# powerpartial_proto2.net
KiCad netlist of a schematic drawn in EAGLE
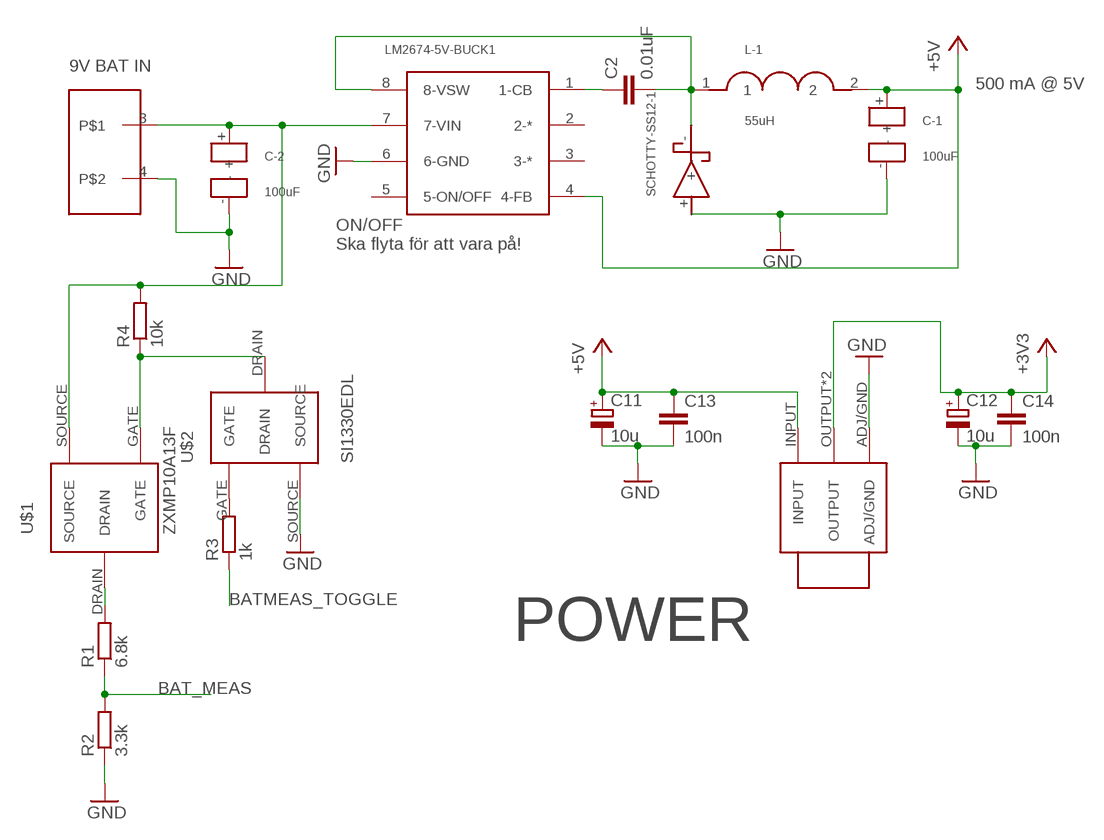
[diagram p0: schematic, sheet 1]

(export (version "E")
  (design (tool "Eeschema 10.0.6"))
  (components
    (comp (ref "C-1")
      (value "100uF")
      (footprint "eagle-import:CAP-6.3MM-DIA")
      (libsource (lib "eagle-import") (part "PANASONIC-CAP"))
    )
    (comp (ref "C-2")
      (value "100uF")
      (footprint "eagle-import:CAP-6.3MM-DIA")
      (libsource (lib "eagle-import") (part "PANASONIC-CAP"))
    )
    (comp (ref "C2")
      (value "0.01uF")
      (footprint "eagle-import:C0805")
      (libsource (lib "eagle-import") (part "C-EUC0805"))
    )
    (comp (ref "C11")
      (value "10u")
      (footprint "eagle-import:153CLV-0505")
      (libsource (lib "eagle-import") (part "CPOL-EU153CLV-0505"))
    )
    (comp (ref "C12")
      (value "10u")
      (footprint "eagle-import:153CLV-0505")
      (libsource (lib "eagle-import") (part "CPOL-EU153CLV-0505"))
    )
    (comp (ref "C13")
      (value "100n")
      (footprint "eagle-import:C0805")
      (libsource (lib "eagle-import") (part "C-EUC0805"))
    )
    (comp (ref "C14")
      (value "100n")
      (footprint "eagle-import:C0805")
      (libsource (lib "eagle-import") (part "C-EUC0805"))
    )
    (comp (ref "L-1")
      (value "55uH")
      (footprint "eagle-import:INDUCTOR")
      (libsource (lib "eagle-import") (part "55UH-INDUKTOR"))
    )
    (comp (ref "LM1117-1")
      (value "LM1117")
      (footprint "eagle-import:LM1117")
      (libsource (lib "eagle-import") (part "LM1117"))
    )
    (comp (ref "LM2674-5V-BUCK1")
      (value "LM2674-5VBUCK")
      (footprint "eagle-import:LM2674")
      (libsource (lib "eagle-import") (part "LM2674-5VBUCK"))
    )
    (comp (ref "R1")
      (value "6.8k")
      (footprint "eagle-import:R0805")
      (libsource (lib "eagle-import") (part "R-EU_R0805"))
    )
    (comp (ref "R2")
      (value "3.3k")
      (footprint "eagle-import:R0805")
      (libsource (lib "eagle-import") (part "R-EU_R0805"))
    )
    (comp (ref "R3")
      (value "1k")
      (footprint "eagle-import:R0805")
      (libsource (lib "eagle-import") (part "R-EU_R0805"))
    )
    (comp (ref "R4")
      (value "10k")
      (footprint "eagle-import:R0805")
      (libsource (lib "eagle-import") (part "R-EU_R0805"))
    )
    (comp (ref "SCHOTTY-SS12-1")
      (value "SCHOTTY-SS12")
      (footprint "eagle-import:SCHOTTY")
      (libsource (lib "eagle-import") (part "SCHOTTY-SS12"))
    )
    (comp (ref "SKRUVPLINT_2P1")
      (value "SKRUVPLINT_2P")
      (footprint "eagle-import:SKRUVPLINT_2P")
      (libsource (lib "eagle-import") (part "SKRUVPLINT_2P"))
    )
    (comp (ref "U$1")
      (value "ZXMP10A13F")
      (footprint "eagle-import:P-CHANNEL")
      (libsource (lib "eagle-import") (part "ZXMP10A13F"))
    )
    (comp (ref "U$2")
      (value "SI1330EDL")
      (footprint "eagle-import:SOT-323")
      (libsource (lib "eagle-import") (part "SI1330EDL"))
    )
  )
  (nets
    (net (code "1") (name "+3V3") (class "Default")
      (node (ref "C12") (pin "+") (pinfunction "+_+") (pintype "passive"))
      (node (ref "C14") (pin "1") (pinfunction "1_1") (pintype "passive"))
      (node (ref "LM1117-1") (pin "OUTPUT") (pinfunction "OUTPUT_OUTPUT") (pintype "bidirectional"))
      (node (ref "LM1117-1") (pin "OUTPUT2") (pinfunction "OUTPUT_OUTPUT2") (pintype "bidirectional"))
    )
    (net (code "2") (name "+5V") (class "Default")
      (node (ref "C-1") (pin "+") (pinfunction "+_+") (pintype "bidirectional"))
      (node (ref "C11") (pin "+") (pinfunction "+_+") (pintype "passive"))
      (node (ref "C13") (pin "1") (pinfunction "1_1") (pintype "passive"))
      (node (ref "L-1") (pin "2") (pinfunction "2_2") (pintype "bidirectional"))
      (node (ref "LM1117-1") (pin "INPUT") (pinfunction "INPUT_INPUT") (pintype "bidirectional"))
      (node (ref "LM2674-5V-BUCK1") (pin "4") (pinfunction "4-FB_4") (pintype "bidirectional"))
    )
    (net (code "3") (name "/BATMEAS_TOGGLE") (class "Default")
      (node (ref "R3") (pin "1") (pinfunction "1_1") (pintype "passive"))
    )
    (net (code "4") (name "/BAT_MEAS") (class "Default")
      (node (ref "R1") (pin "1") (pinfunction "1_1") (pintype "passive"))
      (node (ref "R2") (pin "2") (pinfunction "2_2") (pintype "passive"))
    )
    (net (code "5") (name "GND") (class "Default")
      (node (ref "C-1") (pin "-") (pinfunction "-_-") (pintype "bidirectional"))
      (node (ref "C-2") (pin "-") (pinfunction "-_-") (pintype "bidirectional"))
      (node (ref "C11") (pin "-") (pinfunction "-_-") (pintype "passive"))
      (node (ref "C12") (pin "-") (pinfunction "-_-") (pintype "passive"))
      (node (ref "C13") (pin "2") (pinfunction "2_2") (pintype "passive"))
      (node (ref "C14") (pin "2") (pinfunction "2_2") (pintype "passive"))
      (node (ref "LM1117-1") (pin "ADJ/GND") (pinfunction "ADJ/GND_ADJ/GND") (pintype "bidirectional"))
      (node (ref "LM2674-5V-BUCK1") (pin "6") (pinfunction "6-GND_6") (pintype "bidirectional"))
      (node (ref "R2") (pin "1") (pinfunction "1_1") (pintype "passive"))
      (node (ref "SCHOTTY-SS12-1") (pin "+") (pinfunction "+_+") (pintype "bidirectional"))
      (node (ref "SKRUVPLINT_2P1") (pin "4") (pinfunction "P$2_4") (pintype "bidirectional"))
      (node (ref "U$2") (pin "SOURCE") (pinfunction "SOURCE_SOURCE") (pintype "bidirectional"))
    )
    (net (code "6") (name "Net-(LM2674-5V-BUCK1-1-CB)") (class "Default")
      (node (ref "C2") (pin "1") (pinfunction "1_1") (pintype "passive"))
      (node (ref "LM2674-5V-BUCK1") (pin "1") (pinfunction "1-CB_1") (pintype "bidirectional"))
    )
    (net (code "7") (name "Net-(LM2674-5V-BUCK1-7-VIN)") (class "Default")
      (node (ref "C-2") (pin "+") (pinfunction "+_+") (pintype "bidirectional"))
      (node (ref "LM2674-5V-BUCK1") (pin "7") (pinfunction "7-VIN_7") (pintype "bidirectional"))
      (node (ref "R4") (pin "2") (pinfunction "2_2") (pintype "passive"))
      (node (ref "SKRUVPLINT_2P1") (pin "3") (pinfunction "P$1_3") (pintype "bidirectional"))
      (node (ref "U$1") (pin "SOURCE") (pinfunction "SOURCE_SOURCE") (pintype "bidirectional"))
    )
    (net (code "8") (name "Net-(LM2674-5V-BUCK1-8-VSW)") (class "Default")
      (node (ref "C2") (pin "2") (pinfunction "2_2") (pintype "passive"))
      (node (ref "L-1") (pin "1") (pinfunction "1_1") (pintype "bidirectional"))
      (node (ref "LM2674-5V-BUCK1") (pin "8") (pinfunction "8-VSW_8") (pintype "bidirectional"))
      (node (ref "SCHOTTY-SS12-1") (pin "-") (pinfunction "-_-") (pintype "bidirectional"))
    )
    (net (code "9") (name "Net-(R1-Pad2)") (class "Default")
      (node (ref "R1") (pin "2") (pinfunction "2_2") (pintype "passive"))
      (node (ref "U$1") (pin "DRAIN") (pinfunction "DRAIN_DRAIN") (pintype "bidirectional"))
    )
    (net (code "10") (name "Net-(R3-Pad2)") (class "Default")
      (node (ref "R3") (pin "2") (pinfunction "2_2") (pintype "passive"))
      (node (ref "U$2") (pin "GATE") (pinfunction "GATE_GATE") (pintype "bidirectional"))
    )
    (net (code "11") (name "Net-(R4-Pad1)") (class "Default")
      (node (ref "R4") (pin "1") (pinfunction "1_1") (pintype "passive"))
      (node (ref "U$1") (pin "GATE") (pinfunction "GATE_GATE") (pintype "bidirectional"))
      (node (ref "U$2") (pin "DRAIN") (pinfunction "DRAIN_DRAIN") (pintype "bidirectional"))
    )
    (net (code "12") (name "unconnected-(LM2674-5V-BUCK1-2-*-Pad2)") (class "Default")
      (node (ref "LM2674-5V-BUCK1") (pin "2") (pinfunction "2-*_2") (pintype "bidirectional"))
    )
    (net (code "13") (name "unconnected-(LM2674-5V-BUCK1-3-*-Pad3)") (class "Default")
      (node (ref "LM2674-5V-BUCK1") (pin "3") (pinfunction "3-*_3") (pintype "bidirectional"))
    )
    (net (code "14") (name "unconnected-(LM2674-5V-BUCK1-5-ON{slash}OFF-Pad5)") (class "Default")
      (node (ref "LM2674-5V-BUCK1") (pin "5") (pinfunction "5-ON/OFF_5") (pintype "bidirectional"))
    )
  )
)
